# Surface.net
KiCad netlist of a schematic drawn in Altium Designer
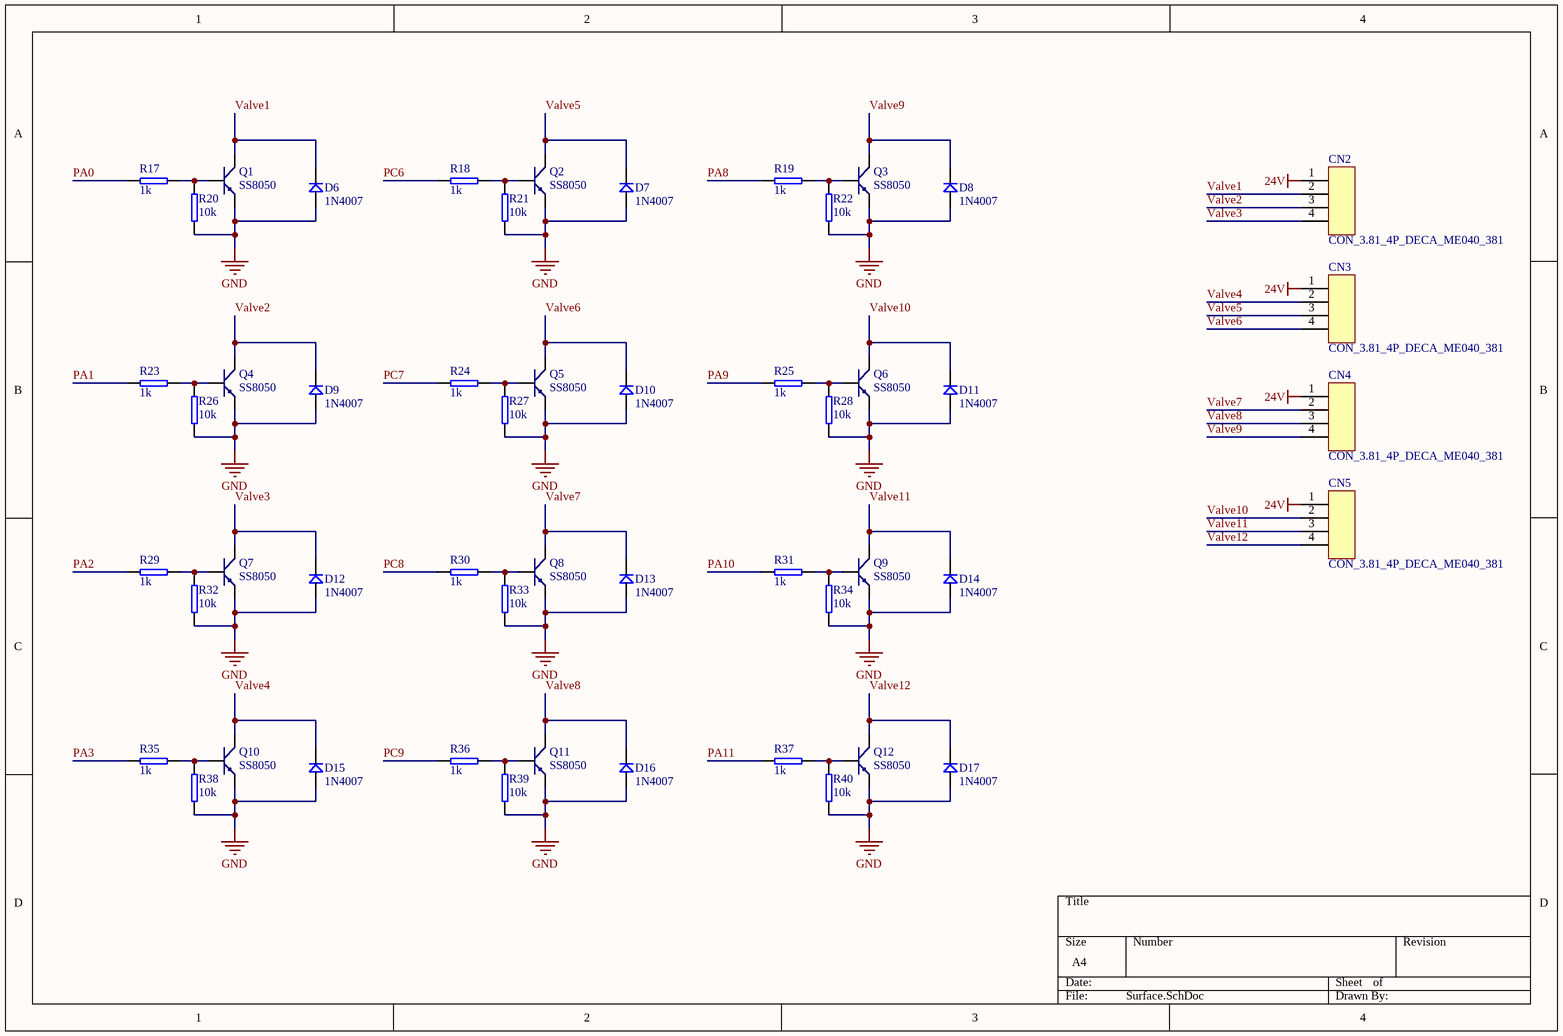
[diagram p0: Surface.SchDoc]

(export (version "E")
  (design (tool "Eeschema 10.0.6"))
  (components
    (comp (ref "CN2")
      (value "CON_3.81_4P_DECA_ME040_381")
      (footprint "ME040_381_4P_VC-1")
      (description "DECA connector,3.81mm,1*4P,180度")
      (fields (field (name "MANUFACTURER") "DECA") (field (name "PARTNUMBER") "ME040-381-4P"))
      (libsource (lib "Schlib1") (part "CON_3.81_4P_DECA_ME040_381"))
    )
    (comp (ref "CN3")
      (value "CON_3.81_4P_DECA_ME040_381")
      (footprint "ME040_381_4P_VC-1")
      (description "DECA connector,3.81mm,1*4P,180度")
      (fields (field (name "MANUFACTURER") "DECA") (field (name "PARTNUMBER") "ME040-381-4P"))
      (libsource (lib "Schlib1") (part "CON_3.81_4P_DECA_ME040_381"))
    )
    (comp (ref "CN4")
      (value "CON_3.81_4P_DECA_ME040_381")
      (footprint "ME040_381_4P_VC-1")
      (description "DECA connector,3.81mm,1*4P,180度")
      (fields (field (name "MANUFACTURER") "DECA") (field (name "PARTNUMBER") "ME040-381-4P"))
      (libsource (lib "Schlib1") (part "CON_3.81_4P_DECA_ME040_381"))
    )
    (comp (ref "CN5")
      (value "CON_3.81_4P_DECA_ME040_381")
      (footprint "ME040_381_4P_VC-1")
      (description "DECA connector,3.81mm,1*4P,180度")
      (fields (field (name "MANUFACTURER") "DECA") (field (name "PARTNUMBER") "ME040-381-4P"))
      (libsource (lib "Schlib1") (part "CON_3.81_4P_DECA_ME040_381"))
    )
    (comp (ref "D6")
      (value "1N4007")
      (footprint "LC-SOD-123")
      (description "1N4148")
      (libsource (lib "stm32_s") (part "D"))
    )
    (comp (ref "D7")
      (value "1N4007")
      (footprint "LC-SOD-123")
      (description "1N4148")
      (libsource (lib "stm32_s") (part "D"))
    )
    (comp (ref "D8")
      (value "1N4007")
      (footprint "LC-SOD-123")
      (description "1N4148")
      (libsource (lib "stm32_s") (part "D"))
    )
    (comp (ref "D9")
      (value "1N4007")
      (footprint "LC-SOD-123")
      (description "1N4148")
      (libsource (lib "stm32_s") (part "D"))
    )
    (comp (ref "D10")
      (value "1N4007")
      (footprint "LC-SOD-123")
      (description "1N4148")
      (libsource (lib "stm32_s") (part "D"))
    )
    (comp (ref "D11")
      (value "1N4007")
      (footprint "LC-SOD-123")
      (description "1N4148")
      (libsource (lib "stm32_s") (part "D"))
    )
    (comp (ref "D12")
      (value "1N4007")
      (footprint "LC-SOD-123")
      (description "1N4148")
      (libsource (lib "stm32_s") (part "D"))
    )
    (comp (ref "D13")
      (value "1N4007")
      (footprint "LC-SOD-123")
      (description "1N4148")
      (libsource (lib "stm32_s") (part "D"))
    )
    (comp (ref "D14")
      (value "1N4007")
      (footprint "LC-SOD-123")
      (description "1N4148")
      (libsource (lib "stm32_s") (part "D"))
    )
    (comp (ref "D15")
      (value "1N4007")
      (footprint "LC-SOD-123")
      (description "1N4148")
      (libsource (lib "stm32_s") (part "D"))
    )
    (comp (ref "D16")
      (value "1N4007")
      (footprint "LC-SOD-123")
      (description "1N4148")
      (libsource (lib "stm32_s") (part "D"))
    )
    (comp (ref "D17")
      (value "1N4007")
      (footprint "LC-SOD-123")
      (description "1N4148")
      (libsource (lib "stm32_s") (part "D"))
    )
    (comp (ref "Q1")
      (value "SS8050")
      (footprint "SOT-23R")
      (description "8050/BCW846/BCW847")
      (libsource (lib "stm32_s") (part "NPN"))
    )
    (comp (ref "Q2")
      (value "SS8050")
      (footprint "SOT-23R")
      (description "8050/BCW846/BCW847")
      (libsource (lib "stm32_s") (part "NPN"))
    )
    (comp (ref "Q3")
      (value "SS8050")
      (footprint "SOT-23R")
      (description "8050/BCW846/BCW847")
      (libsource (lib "stm32_s") (part "NPN"))
    )
    (comp (ref "Q4")
      (value "SS8050")
      (footprint "SOT-23R")
      (description "8050/BCW846/BCW847")
      (libsource (lib "stm32_s") (part "NPN"))
    )
    (comp (ref "Q5")
      (value "SS8050")
      (footprint "SOT-23R")
      (description "8050/BCW846/BCW847")
      (libsource (lib "stm32_s") (part "NPN"))
    )
    (comp (ref "Q6")
      (value "SS8050")
      (footprint "SOT-23R")
      (description "8050/BCW846/BCW847")
      (libsource (lib "stm32_s") (part "NPN"))
    )
    (comp (ref "Q7")
      (value "SS8050")
      (footprint "SOT-23R")
      (description "8050/BCW846/BCW847")
      (libsource (lib "stm32_s") (part "NPN"))
    )
    (comp (ref "Q8")
      (value "SS8050")
      (footprint "SOT-23R")
      (description "8050/BCW846/BCW847")
      (libsource (lib "stm32_s") (part "NPN"))
    )
    (comp (ref "Q9")
      (value "SS8050")
      (footprint "SOT-23R")
      (description "8050/BCW846/BCW847")
      (libsource (lib "stm32_s") (part "NPN"))
    )
    (comp (ref "Q10")
      (value "SS8050")
      (footprint "SOT-23R")
      (description "8050/BCW846/BCW847")
      (libsource (lib "stm32_s") (part "NPN"))
    )
    (comp (ref "Q11")
      (value "SS8050")
      (footprint "SOT-23R")
      (description "8050/BCW846/BCW847")
      (libsource (lib "stm32_s") (part "NPN"))
    )
    (comp (ref "Q12")
      (value "SS8050")
      (footprint "SOT-23R")
      (description "8050/BCW846/BCW847")
      (libsource (lib "stm32_s") (part "NPN"))
    )
    (comp (ref "R17")
      (value "1k")
      (footprint "R0603")
      (description "标贴电阻")
      (libsource (lib "stm32_s") (part "R"))
    )
    (comp (ref "R18")
      (value "1k")
      (footprint "R0603")
      (description "标贴电阻")
      (libsource (lib "stm32_s") (part "R"))
    )
    (comp (ref "R19")
      (value "1k")
      (footprint "R0603")
      (description "标贴电阻")
      (libsource (lib "stm32_s") (part "R"))
    )
    (comp (ref "R20")
      (value "10k")
      (footprint "R0603")
      (description "标贴电阻")
      (libsource (lib "stm32_s") (part "R"))
    )
    (comp (ref "R21")
      (value "10k")
      (footprint "R0603")
      (description "标贴电阻")
      (libsource (lib "stm32_s") (part "R"))
    )
    (comp (ref "R22")
      (value "10k")
      (footprint "R0603")
      (description "标贴电阻")
      (libsource (lib "stm32_s") (part "R"))
    )
    (comp (ref "R23")
      (value "1k")
      (footprint "R0603")
      (description "标贴电阻")
      (libsource (lib "stm32_s") (part "R"))
    )
    (comp (ref "R24")
      (value "1k")
      (footprint "R0603")
      (description "标贴电阻")
      (libsource (lib "stm32_s") (part "R"))
    )
    (comp (ref "R25")
      (value "1k")
      (footprint "R0603")
      (description "标贴电阻")
      (libsource (lib "stm32_s") (part "R"))
    )
    (comp (ref "R26")
      (value "10k")
      (footprint "R0603")
      (description "标贴电阻")
      (libsource (lib "stm32_s") (part "R"))
    )
    (comp (ref "R27")
      (value "10k")
      (footprint "R0603")
      (description "标贴电阻")
      (libsource (lib "stm32_s") (part "R"))
    )
    (comp (ref "R28")
      (value "10k")
      (footprint "R0603")
      (description "标贴电阻")
      (libsource (lib "stm32_s") (part "R"))
    )
    (comp (ref "R29")
      (value "1k")
      (footprint "R0603")
      (description "标贴电阻")
      (libsource (lib "stm32_s") (part "R"))
    )
    (comp (ref "R30")
      (value "1k")
      (footprint "R0603")
      (description "标贴电阻")
      (libsource (lib "stm32_s") (part "R"))
    )
    (comp (ref "R31")
      (value "1k")
      (footprint "R0603")
      (description "标贴电阻")
      (libsource (lib "stm32_s") (part "R"))
    )
    (comp (ref "R32")
      (value "10k")
      (footprint "R0603")
      (description "标贴电阻")
      (libsource (lib "stm32_s") (part "R"))
    )
    (comp (ref "R33")
      (value "10k")
      (footprint "R0603")
      (description "标贴电阻")
      (libsource (lib "stm32_s") (part "R"))
    )
    (comp (ref "R34")
      (value "10k")
      (footprint "R0603")
      (description "标贴电阻")
      (libsource (lib "stm32_s") (part "R"))
    )
    (comp (ref "R35")
      (value "1k")
      (footprint "R0603")
      (description "标贴电阻")
      (libsource (lib "stm32_s") (part "R"))
    )
    (comp (ref "R36")
      (value "1k")
      (footprint "R0603")
      (description "标贴电阻")
      (libsource (lib "stm32_s") (part "R"))
    )
    (comp (ref "R37")
      (value "1k")
      (footprint "R0603")
      (description "标贴电阻")
      (libsource (lib "stm32_s") (part "R"))
    )
    (comp (ref "R38")
      (value "10k")
      (footprint "R0603")
      (description "标贴电阻")
      (libsource (lib "stm32_s") (part "R"))
    )
    (comp (ref "R39")
      (value "10k")
      (footprint "R0603")
      (description "标贴电阻")
      (libsource (lib "stm32_s") (part "R"))
    )
    (comp (ref "R40")
      (value "10k")
      (footprint "R0603")
      (description "标贴电阻")
      (libsource (lib "stm32_s") (part "R"))
    )
  )
  (nets
    (net (code "1") (name "/PA0") (class "Default")
      (node (ref "R17") (pin "2") (pinfunction "2_2") (pintype "passive"))
    )
    (net (code "2") (name "/PA1") (class "Default")
      (node (ref "R23") (pin "2") (pinfunction "2_2") (pintype "passive"))
    )
    (net (code "3") (name "/PA2") (class "Default")
      (node (ref "R29") (pin "2") (pinfunction "2_2") (pintype "passive"))
    )
    (net (code "4") (name "/PA3") (class "Default")
      (node (ref "R35") (pin "2") (pinfunction "2_2") (pintype "passive"))
    )
    (net (code "5") (name "/PA8") (class "Default")
      (node (ref "R19") (pin "2") (pinfunction "2_2") (pintype "passive"))
    )
    (net (code "6") (name "/PA9") (class "Default")
      (node (ref "R25") (pin "2") (pinfunction "2_2") (pintype "passive"))
    )
    (net (code "7") (name "/PA10") (class "Default")
      (node (ref "R31") (pin "2") (pinfunction "2_2") (pintype "passive"))
    )
    (net (code "8") (name "/PA11") (class "Default")
      (node (ref "R37") (pin "2") (pinfunction "2_2") (pintype "passive"))
    )
    (net (code "9") (name "/PC6") (class "Default")
      (node (ref "R18") (pin "2") (pinfunction "2_2") (pintype "passive"))
    )
    (net (code "10") (name "/PC7") (class "Default")
      (node (ref "R24") (pin "2") (pinfunction "2_2") (pintype "passive"))
    )
    (net (code "11") (name "/PC8") (class "Default")
      (node (ref "R30") (pin "2") (pinfunction "2_2") (pintype "passive"))
    )
    (net (code "12") (name "/PC9") (class "Default")
      (node (ref "R36") (pin "2") (pinfunction "2_2") (pintype "passive"))
    )
    (net (code "13") (name "/Valve1") (class "Default")
      (node (ref "CN2") (pin "2") (pinfunction "2_2") (pintype "passive"))
      (node (ref "D6") (pin "2") (pintype "passive"))
      (node (ref "Q1") (pin "3") (pinfunction "C_3") (pintype "passive"))
    )
    (net (code "14") (name "/Valve2") (class "Default")
      (node (ref "CN2") (pin "3") (pinfunction "3_3") (pintype "passive"))
      (node (ref "D9") (pin "2") (pintype "passive"))
      (node (ref "Q4") (pin "3") (pinfunction "C_3") (pintype "passive"))
    )
    (net (code "15") (name "/Valve3") (class "Default")
      (node (ref "CN2") (pin "4") (pinfunction "4_4") (pintype "passive"))
      (node (ref "D12") (pin "2") (pintype "passive"))
      (node (ref "Q7") (pin "3") (pinfunction "C_3") (pintype "passive"))
    )
    (net (code "16") (name "/Valve4") (class "Default")
      (node (ref "CN3") (pin "2") (pinfunction "2_2") (pintype "passive"))
      (node (ref "D15") (pin "2") (pintype "passive"))
      (node (ref "Q10") (pin "3") (pinfunction "C_3") (pintype "passive"))
    )
    (net (code "17") (name "/Valve5") (class "Default")
      (node (ref "CN3") (pin "3") (pinfunction "3_3") (pintype "passive"))
      (node (ref "D7") (pin "2") (pintype "passive"))
      (node (ref "Q2") (pin "3") (pinfunction "C_3") (pintype "passive"))
    )
    (net (code "18") (name "/Valve6") (class "Default")
      (node (ref "CN3") (pin "4") (pinfunction "4_4") (pintype "passive"))
      (node (ref "D10") (pin "2") (pintype "passive"))
      (node (ref "Q5") (pin "3") (pinfunction "C_3") (pintype "passive"))
    )
    (net (code "19") (name "/Valve7") (class "Default")
      (node (ref "CN4") (pin "2") (pinfunction "2_2") (pintype "passive"))
      (node (ref "D13") (pin "2") (pintype "passive"))
      (node (ref "Q8") (pin "3") (pinfunction "C_3") (pintype "passive"))
    )
    (net (code "20") (name "/Valve8") (class "Default")
      (node (ref "CN4") (pin "3") (pinfunction "3_3") (pintype "passive"))
      (node (ref "D16") (pin "2") (pintype "passive"))
      (node (ref "Q11") (pin "3") (pinfunction "C_3") (pintype "passive"))
    )
    (net (code "21") (name "/Valve9") (class "Default")
      (node (ref "CN4") (pin "4") (pinfunction "4_4") (pintype "passive"))
      (node (ref "D8") (pin "2") (pintype "passive"))
      (node (ref "Q3") (pin "3") (pinfunction "C_3") (pintype "passive"))
    )
    (net (code "22") (name "/Valve10") (class "Default")
      (node (ref "CN5") (pin "2") (pinfunction "2_2") (pintype "passive"))
      (node (ref "D11") (pin "2") (pintype "passive"))
      (node (ref "Q6") (pin "3") (pinfunction "C_3") (pintype "passive"))
    )
    (net (code "23") (name "/Valve11") (class "Default")
      (node (ref "CN5") (pin "3") (pinfunction "3_3") (pintype "passive"))
      (node (ref "D14") (pin "2") (pintype "passive"))
      (node (ref "Q9") (pin "3") (pinfunction "C_3") (pintype "passive"))
    )
    (net (code "24") (name "/Valve12") (class "Default")
      (node (ref "CN5") (pin "4") (pinfunction "4_4") (pintype "passive"))
      (node (ref "D17") (pin "2") (pintype "passive"))
      (node (ref "Q12") (pin "3") (pinfunction "C_3") (pintype "passive"))
    )
    (net (code "25") (name "24V") (class "Default")
      (node (ref "CN2") (pin "1") (pinfunction "1_1") (pintype "passive"))
      (node (ref "CN3") (pin "1") (pinfunction "1_1") (pintype "passive"))
      (node (ref "CN4") (pin "1") (pinfunction "1_1") (pintype "passive"))
      (node (ref "CN5") (pin "1") (pinfunction "1_1") (pintype "passive"))
    )
    (net (code "26") (name "GND") (class "Default")
      (node (ref "D10") (pin "1") (pintype "passive"))
      (node (ref "D11") (pin "1") (pintype "passive"))
      (node (ref "D12") (pin "1") (pintype "passive"))
      (node (ref "D13") (pin "1") (pintype "passive"))
      (node (ref "D14") (pin "1") (pintype "passive"))
      (node (ref "D15") (pin "1") (pintype "passive"))
      (node (ref "D16") (pin "1") (pintype "passive"))
      (node (ref "D17") (pin "1") (pintype "passive"))
      (node (ref "D6") (pin "1") (pintype "passive"))
      (node (ref "D7") (pin "1") (pintype "passive"))
      (node (ref "D8") (pin "1") (pintype "passive"))
      (node (ref "D9") (pin "1") (pintype "passive"))
      (node (ref "Q1") (pin "1") (pinfunction "E_1") (pintype "passive"))
      (node (ref "Q10") (pin "1") (pinfunction "E_1") (pintype "passive"))
      (node (ref "Q11") (pin "1") (pinfunction "E_1") (pintype "passive"))
      (node (ref "Q12") (pin "1") (pinfunction "E_1") (pintype "passive"))
      (node (ref "Q2") (pin "1") (pinfunction "E_1") (pintype "passive"))
      (node (ref "Q3") (pin "1") (pinfunction "E_1") (pintype "passive"))
      (node (ref "Q4") (pin "1") (pinfunction "E_1") (pintype "passive"))
      (node (ref "Q5") (pin "1") (pinfunction "E_1") (pintype "passive"))
      (node (ref "Q6") (pin "1") (pinfunction "E_1") (pintype "passive"))
      (node (ref "Q7") (pin "1") (pinfunction "E_1") (pintype "passive"))
      (node (ref "Q8") (pin "1") (pinfunction "E_1") (pintype "passive"))
      (node (ref "Q9") (pin "1") (pinfunction "E_1") (pintype "passive"))
      (node (ref "R20") (pin "2") (pinfunction "2_2") (pintype "passive"))
      (node (ref "R21") (pin "2") (pinfunction "2_2") (pintype "passive"))
      (node (ref "R22") (pin "2") (pinfunction "2_2") (pintype "passive"))
      (node (ref "R26") (pin "2") (pinfunction "2_2") (pintype "passive"))
      (node (ref "R27") (pin "2") (pinfunction "2_2") (pintype "passive"))
      (node (ref "R28") (pin "2") (pinfunction "2_2") (pintype "passive"))
      (node (ref "R32") (pin "2") (pinfunction "2_2") (pintype "passive"))
      (node (ref "R33") (pin "2") (pinfunction "2_2") (pintype "passive"))
      (node (ref "R34") (pin "2") (pinfunction "2_2") (pintype "passive"))
      (node (ref "R38") (pin "2") (pinfunction "2_2") (pintype "passive"))
      (node (ref "R39") (pin "2") (pinfunction "2_2") (pintype "passive"))
      (node (ref "R40") (pin "2") (pinfunction "2_2") (pintype "passive"))
    )
    (net (code "27") (name "Net-(Q1-B)") (class "Default")
      (node (ref "Q1") (pin "2") (pinfunction "B_2") (pintype "passive"))
      (node (ref "R17") (pin "1") (pinfunction "1_1") (pintype "passive"))
      (node (ref "R20") (pin "1") (pinfunction "1_1") (pintype "passive"))
    )
    (net (code "28") (name "Net-(Q2-B)") (class "Default")
      (node (ref "Q2") (pin "2") (pinfunction "B_2") (pintype "passive"))
      (node (ref "R18") (pin "1") (pinfunction "1_1") (pintype "passive"))
      (node (ref "R21") (pin "1") (pinfunction "1_1") (pintype "passive"))
    )
    (net (code "29") (name "Net-(Q3-B)") (class "Default")
      (node (ref "Q3") (pin "2") (pinfunction "B_2") (pintype "passive"))
      (node (ref "R19") (pin "1") (pinfunction "1_1") (pintype "passive"))
      (node (ref "R22") (pin "1") (pinfunction "1_1") (pintype "passive"))
    )
    (net (code "30") (name "Net-(Q4-B)") (class "Default")
      (node (ref "Q4") (pin "2") (pinfunction "B_2") (pintype "passive"))
      (node (ref "R23") (pin "1") (pinfunction "1_1") (pintype "passive"))
      (node (ref "R26") (pin "1") (pinfunction "1_1") (pintype "passive"))
    )
    (net (code "31") (name "Net-(Q5-B)") (class "Default")
      (node (ref "Q5") (pin "2") (pinfunction "B_2") (pintype "passive"))
      (node (ref "R24") (pin "1") (pinfunction "1_1") (pintype "passive"))
      (node (ref "R27") (pin "1") (pinfunction "1_1") (pintype "passive"))
    )
    (net (code "32") (name "Net-(Q6-B)") (class "Default")
      (node (ref "Q6") (pin "2") (pinfunction "B_2") (pintype "passive"))
      (node (ref "R25") (pin "1") (pinfunction "1_1") (pintype "passive"))
      (node (ref "R28") (pin "1") (pinfunction "1_1") (pintype "passive"))
    )
    (net (code "33") (name "Net-(Q7-B)") (class "Default")
      (node (ref "Q7") (pin "2") (pinfunction "B_2") (pintype "passive"))
      (node (ref "R29") (pin "1") (pinfunction "1_1") (pintype "passive"))
      (node (ref "R32") (pin "1") (pinfunction "1_1") (pintype "passive"))
    )
    (net (code "34") (name "Net-(Q8-B)") (class "Default")
      (node (ref "Q8") (pin "2") (pinfunction "B_2") (pintype "passive"))
      (node (ref "R30") (pin "1") (pinfunction "1_1") (pintype "passive"))
      (node (ref "R33") (pin "1") (pinfunction "1_1") (pintype "passive"))
    )
    (net (code "35") (name "Net-(Q9-B)") (class "Default")
      (node (ref "Q9") (pin "2") (pinfunction "B_2") (pintype "passive"))
      (node (ref "R31") (pin "1") (pinfunction "1_1") (pintype "passive"))
      (node (ref "R34") (pin "1") (pinfunction "1_1") (pintype "passive"))
    )
    (net (code "36") (name "Net-(Q10-B)") (class "Default")
      (node (ref "Q10") (pin "2") (pinfunction "B_2") (pintype "passive"))
      (node (ref "R35") (pin "1") (pinfunction "1_1") (pintype "passive"))
      (node (ref "R38") (pin "1") (pinfunction "1_1") (pintype "passive"))
    )
    (net (code "37") (name "Net-(Q11-B)") (class "Default")
      (node (ref "Q11") (pin "2") (pinfunction "B_2") (pintype "passive"))
      (node (ref "R36") (pin "1") (pinfunction "1_1") (pintype "passive"))
      (node (ref "R39") (pin "1") (pinfunction "1_1") (pintype "passive"))
    )
    (net (code "38") (name "Net-(Q12-B)") (class "Default")
      (node (ref "Q12") (pin "2") (pinfunction "B_2") (pintype "passive"))
      (node (ref "R37") (pin "1") (pinfunction "1_1") (pintype "passive"))
      (node (ref "R40") (pin "1") (pinfunction "1_1") (pintype "passive"))
    )
  )
)
